# BUCK_BOOST_Converter.net
KiCad netlist of a schematic drawn in Altium Designer
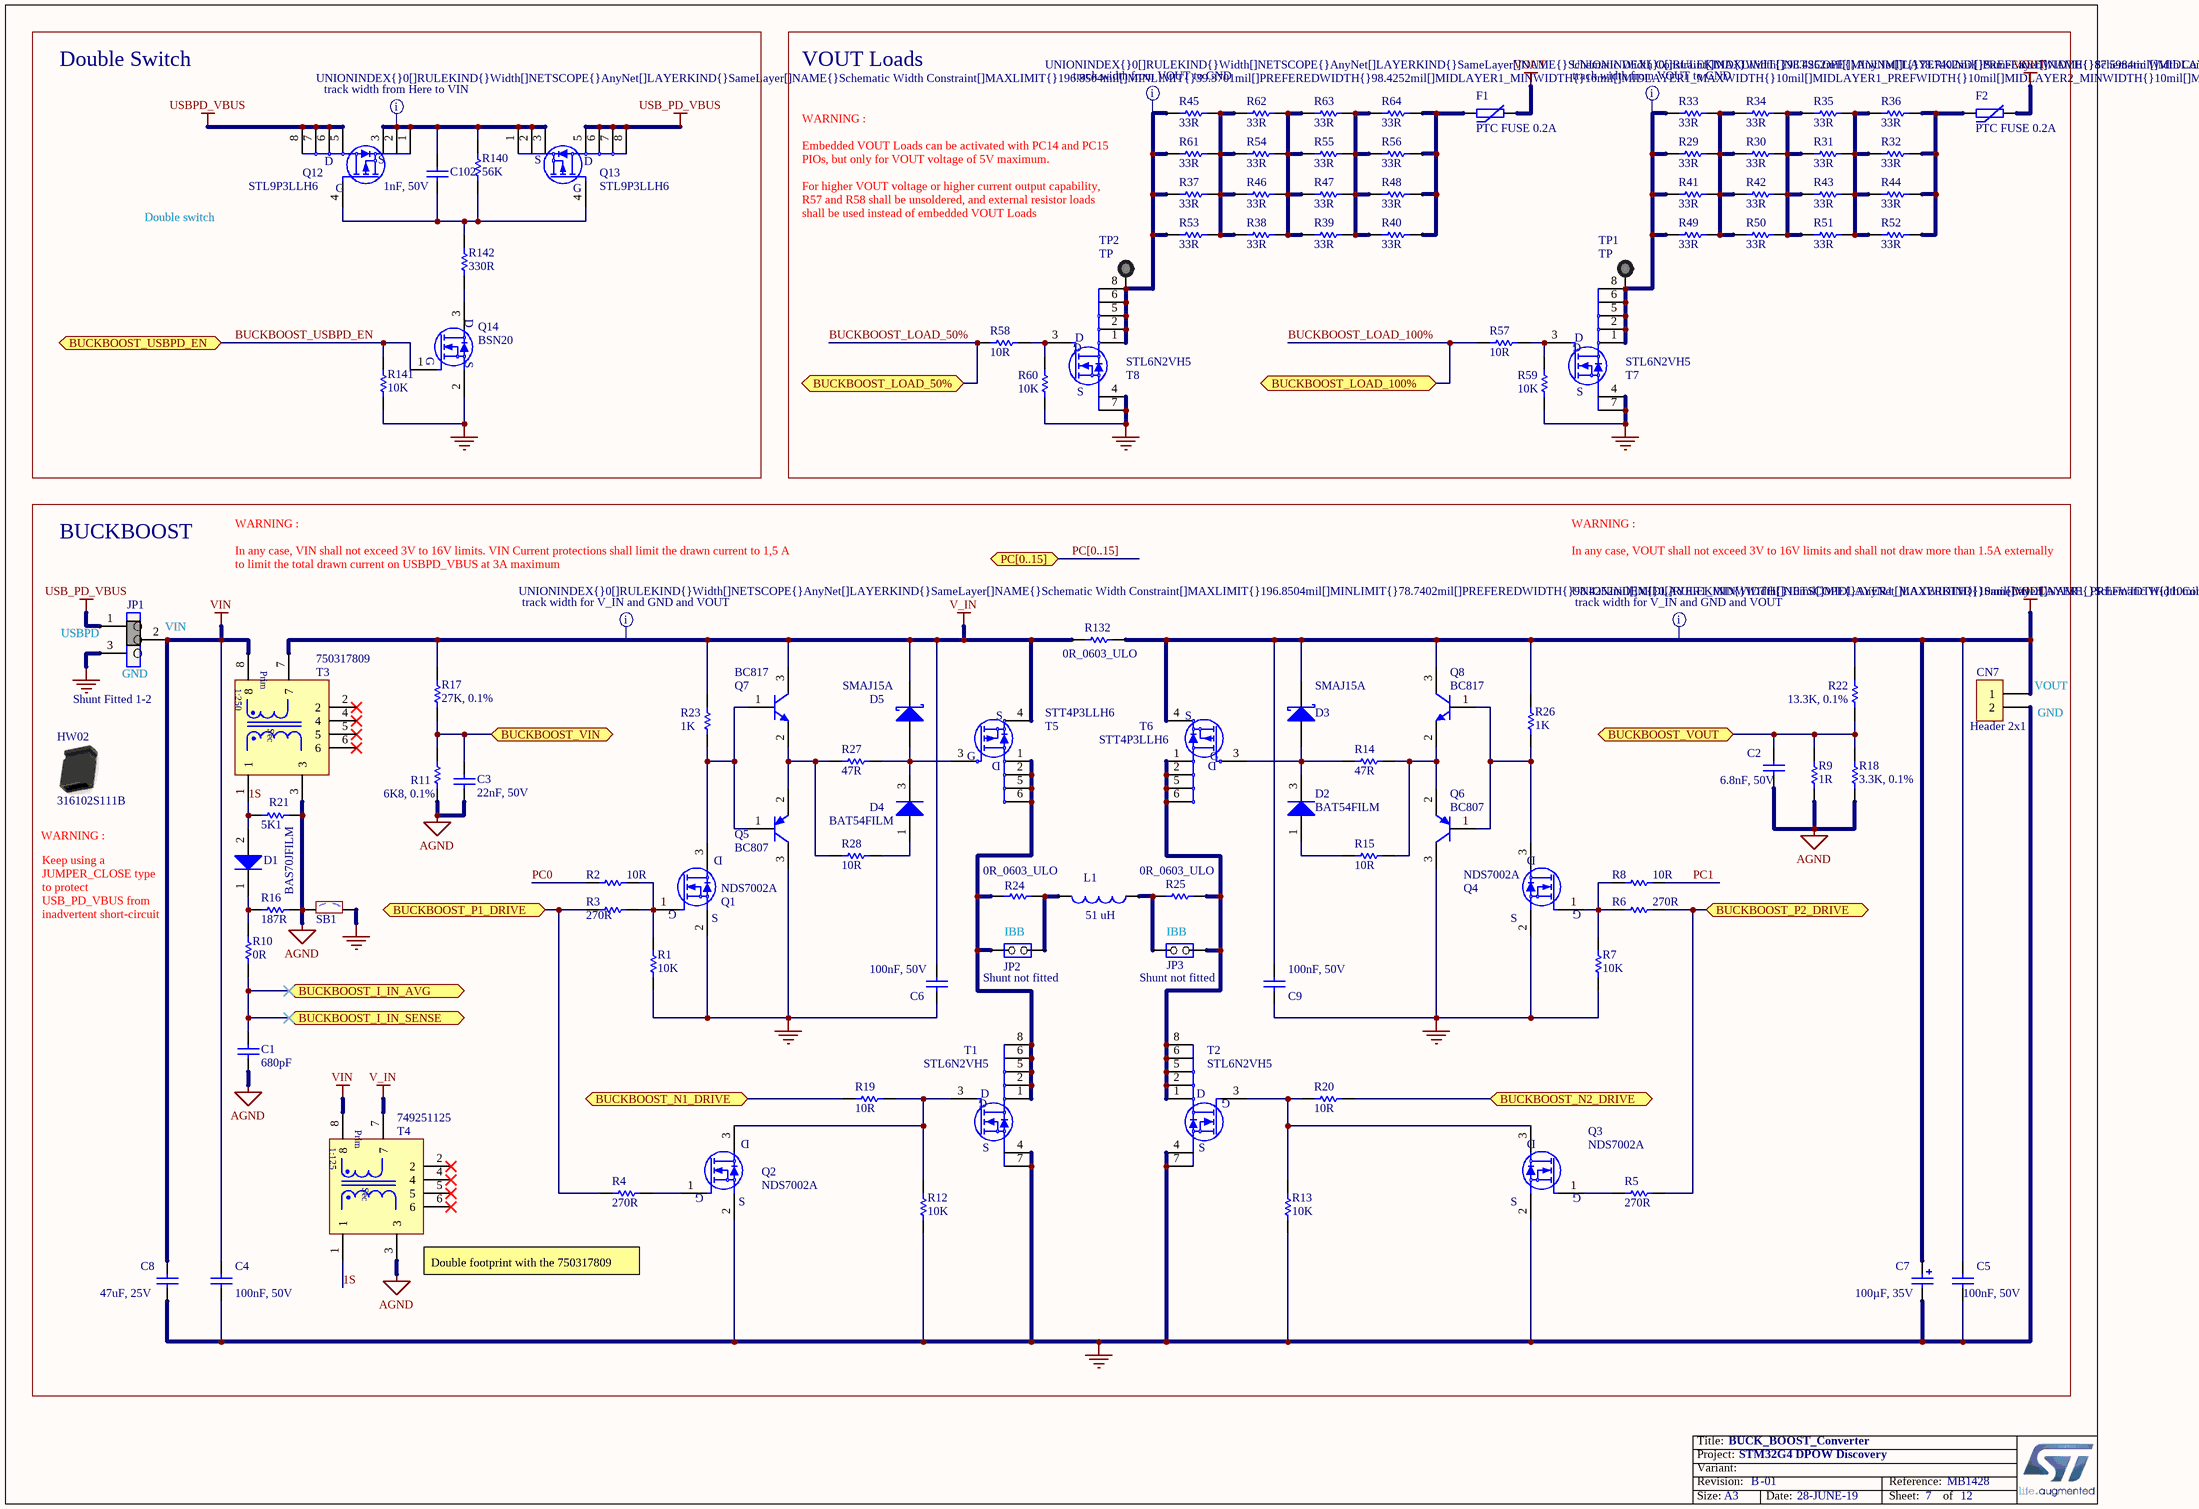
[diagram p0: BUCK_BOOST_Converter.SchDoc]

(export (version "E")
  (design (tool "Eeschema 10.0.6"))
  (components
    (comp (ref "C1")
      (value "680pF")
      (footprint "C0603_H0P8")
      (description "Capacitor, MLCC, 680pF, 16V, X7R, 10%, 0603, T=0.8mm")
      (fields
        (field (name "INTERNAL_PART_NUMBER") "MCD-01576")
        (field (name "MANUFACTURER_PART_NUMBER") "CC0603KRX7R7BB681")
        (field (name "PROVIDED_BY") "SUBCO")
      )
      (libsource (lib "MCD_PARTS_database") (part "Capacitor"))
    )
    (comp (ref "C2")
      (value "6.8nF, 50V")
      (footprint "C0603_H0P8")
      (description "Capacitor, MLCC, 6.8nF, 50V, X7R, 10%, 0603, T=0.8mm")
      (fields
        (field (name "INTERNAL_PART_NUMBER") "MCD-01544")
        (field (name "MANUFACTURER_PART_NUMBER") "CC0603KRX7R9BB682")
        (field (name "PROVIDED_BY") "SUBCO")
      )
      (libsource (lib "MCD_PARTS_database") (part "Capacitor"))
    )
    (comp (ref "C3")
      (value "22nF, 50V")
      (footprint "C0603")
      (description "Capacitor,22nF,50V,X7R,10%,0603")
      (fields
        (field (name "INTERNAL_PART_NUMBER") "MCD-01103")
        (field (name "MANUFACTURER_PART_NUMBER") "CC0603KRX7R9BB223")
        (field (name "PROVIDED_BY") "SUBCO")
      )
      (libsource (lib "MCD_PARTS_database") (part "Capacitor"))
    )
    (comp (ref "C4")
      (value "100nF, 50V")
      (footprint "C0805_H0P85")
      (description "Capacitor, MLCC, 100nF, 50V, X7R, 10%, 0805, T=0,85mm")
      (fields
        (field (name "INTERNAL_PART_NUMBER") "MCD-01525")
        (field (name "MANUFACTURER_PART_NUMBER") "CC0805KRX7R9BB104")
        (field (name "PROVIDED_BY") "SUBCO")
      )
      (libsource (lib "MCD_PARTS_database") (part "Capacitor"))
    )
    (comp (ref "C5")
      (value "100nF, 50V")
      (footprint "C0805_H0P85")
      (description "Capacitor, MLCC, 100nF, 50V, X7R, 10%, 0805, T=0,85mm")
      (fields
        (field (name "INTERNAL_PART_NUMBER") "MCD-01525")
        (field (name "MANUFACTURER_PART_NUMBER") "CC0805KRX7R9BB104")
        (field (name "PROVIDED_BY") "SUBCO")
      )
      (libsource (lib "MCD_PARTS_database") (part "Capacitor"))
    )
    (comp (ref "C6")
      (value "100nF, 50V")
      (footprint "C0805_H0P85")
      (description "Capacitor, MLCC, 100nF, 50V, X7R, 10%, 0805, T=0,85mm")
      (fields
        (field (name "INTERNAL_PART_NUMBER") "MCD-01525")
        (field (name "MANUFACTURER_PART_NUMBER") "CC0805KRX7R9BB104")
        (field (name "PROVIDED_BY") "SUBCO")
      )
      (libsource (lib "MCD_PARTS_database") (part "Capacitor"))
    )
    (comp (ref "C7")
      (value "100µF, 35V")
      (footprint "CPOL_WURTH_WCAP-ASLL_8X10P5")
      (description "Capacitor, Electrolytic, 100µF, 35V, 20%, SMT, D=8mm, T=10.5mm")
      (fields
        (field (name "INTERNAL_PART_NUMBER") "MCD-01683")
        (field (name "MANUFACTURER_PART_NUMBER") "865060553006")
        (field (name "PROVIDED_BY") "SUBCO")
      )
      (libsource (lib "MCD_PARTS_database") (part "Cap_POL_TANA"))
    )
    (comp (ref "C8")
      (value "47uF, 25V")
      (footprint "C1206_H1P6")
      (description "Capacitor, MLCC, 47uF, 25V, X5R, 20%, 1206, T=1,6mm")
      (fields
        (field (name "INTERNAL_PART_NUMBER") "MCD-01517")
        (field (name "MANUFACTURER_PART_NUMBER") "C3216X5R1E476M160AC ")
        (field (name "PROVIDED_BY") "SUBCO")
      )
      (libsource (lib "MCD_PARTS_database") (part "Capacitor"))
    )
    (comp (ref "C9")
      (value "100nF, 50V")
      (footprint "C0805_H0P85")
      (description "Capacitor, MLCC, 100nF, 50V, X7R, 10%, 0805, T=0,85mm")
      (fields
        (field (name "INTERNAL_PART_NUMBER") "MCD-01525")
        (field (name "MANUFACTURER_PART_NUMBER") "CC0805KRX7R9BB104")
        (field (name "PROVIDED_BY") "SUBCO")
      )
      (libsource (lib "MCD_PARTS_database") (part "Capacitor"))
    )
    (comp (ref "C102")
      (value "1nF, 50V")
      (footprint "C0805_H0P6")
      (description "Capacitor, MLCC, 1nF, 50V, X7R,10%, 0805, T=0,6mm")
      (fields
        (field (name "INTERNAL_PART_NUMBER") "MCD-01549")
        (field (name "MANUFACTURER_PART_NUMBER") "CC0805KRX7R9BB102")
        (field (name "PROVIDED_BY") "SUBCO")
      )
      (libsource (lib "MCD_PARTS_database") (part "Capacitor"))
    )
    (comp (ref "CN7")
      (value "Header 2x1")
      (footprint "CON_LYCONN_313102S141346")
      (description "Header 2x1, 2.54mm, VR, TH, height 5.84mm/7.50 mm, height total 15.84 mm")
      (fields
        (field (name "INTERNAL_PART_NUMBER") "MCD-01855")
        (field (name "MANUFACTURER_PART_NUMBER") "313102S1411584")
        (field (name "PROVIDED_BY") "SUBCO")
      )
      (libsource (lib "MCD_PARTS_database") (part "Header 2x1"))
    )
    (comp (ref "D1")
      (value "BAS70JFILM")
      (footprint "DIO_SOD323_1K_2A")
      (description "ultrafast and RF switching diode, VF = 0.41 V @ IF = 1mA; VR = 70V;")
      (fields
        (field (name "INTERNAL_PART_NUMBER") "MCD-01880")
        (field (name "MANUFACTURER") "STMICROELECTRONICS")
        (field (name "PROVIDED_BY") "SUBCO with ST control")
      )
      (libsource (lib "MCD_PARTS_database") (part "DIODE_1K_2A"))
    )
    (comp (ref "D2")
      (value "BAT54FILM")
      (footprint "DIO_SOT23_SC59_1A_2NC_3K_H1P4")
      (description "Single surface mount small signal schotky diode")
      (fields
        (field (name "INTERNAL_PART_NUMBER") "MCD-01524")
        (field (name "MANUFACTURER") "STMICROELECTRONICS")
        (field (name "PROVIDED_BY") "SUBCO with ST control")
      )
      (libsource (lib "MCD_PARTS_database") (part "DIODE_SOT23"))
    )
    (comp (ref "D3")
      (value "SMAJ15A")
      (footprint "DIO_SMA_1A_2K")
      (description "Transil unidirectional diode Vrm=15V, Vbr=16.7V(1mA), Vcl=32.5V(71A), SMA")
      (fields
        (field (name "INTERNAL_PART_NUMBER") "MCD-01522")
        (field (name "MANUFACTURER_PART_NUMBER") "SMAJ15A-TR")
        (field (name "PROVIDED_BY") "SUBCO with ST control")
      )
      (libsource (lib "MCD_PARTS_database") (part "ESD-TRANSIL-SMAJ_1A_2K"))
    )
    (comp (ref "D4")
      (value "BAT54FILM")
      (footprint "DIO_SOT23_SC59_1A_2NC_3K_H1P4")
      (description "Single surface mount small signal schotky diode")
      (fields
        (field (name "INTERNAL_PART_NUMBER") "MCD-01524")
        (field (name "MANUFACTURER") "STMICROELECTRONICS")
        (field (name "PROVIDED_BY") "SUBCO with ST control")
      )
      (libsource (lib "MCD_PARTS_database") (part "DIODE_SOT23"))
    )
    (comp (ref "D5")
      (value "SMAJ15A")
      (footprint "DIO_SMA_1A_2K")
      (description "Transil unidirectional diode Vrm=15V, Vbr=16.7V(1mA), Vcl=32.5V(71A), SMA")
      (fields
        (field (name "INTERNAL_PART_NUMBER") "MCD-01522")
        (field (name "MANUFACTURER_PART_NUMBER") "SMAJ15A-TR")
        (field (name "PROVIDED_BY") "SUBCO with ST control")
      )
      (libsource (lib "MCD_PARTS_database") (part "ESD-TRANSIL-SMAJ_1A_2K"))
    )
    (comp (ref "F1")
      (value "PTC FUSE 0.2A")
      (footprint "PTC_EATON_FUSE_PTS1812_H0P9")
      (description "SMD, PTC resettable fuse, IH:0.2A, IT:0.4A, Vdc_max:30V, Rmax:5 ohm")
      (fields
        (field (name "INTERNAL_PART_NUMBER") "MCD-01682")
        (field (name "MANUFACTURER_PART_NUMBER") "PTS181230V020")
        (field (name "PROVIDED_BY") "SUBCO")
      )
      (libsource (lib "MCD_PARTS_database") (part "0ZCG0260FF2C"))
    )
    (comp (ref "F2")
      (value "PTC FUSE 0.2A")
      (footprint "PTC_EATON_FUSE_PTS1812_H0P9")
      (description "SMD, PTC resettable fuse, IH:0.2A, IT:0.4A, Vdc_max:30V, Rmax:5 ohm")
      (fields
        (field (name "INTERNAL_PART_NUMBER") "MCD-01682")
        (field (name "MANUFACTURER_PART_NUMBER") "PTS181230V020")
        (field (name "PROVIDED_BY") "SUBCO")
      )
      (libsource (lib "MCD_PARTS_database") (part "0ZCG0260FF2C"))
    )
    (comp (ref "HW02")
      (value "316102S111B")
      (description "Jumper, height 6.5 mm, Black, 2.54mm, 3A, 20 mohm, close")
      (fields
        (field (name "INTERNAL_PART_NUMBER") "MCD-01864")
        (field (name "MANUFACTURER") "JIUBABA")
        (field (name "PROVIDED_BY") "SUBCO")
      )
      (libsource (lib "MCD_PARTS_database") (part "JUMPER_CLOSE"))
    )
    (comp (ref "JP1")
      (value "Shunt Fitted 1-2")
      (footprint "CON_SAMTEC_TSW-103-07-F-S")
      (description "Header, 3x1, 2,54mm, VR, TH, Height 5.84mm/2.54mm - Shunt Fitted 1-2 by default")
      (fields
        (field (name "INTERNAL_PART_NUMBER") "MCD-00684")
        (field (name "MANUFACTURER_PART_NUMBER") "TSW-103-07-F-S")
        (field (name "PROVIDED_BY") "SUBCO")
      )
      (libsource (lib "MCD_PARTS_database") (part "Jumper_Header 3x1 Fitted 1-2"))
    )
    (comp (ref "JP2")
      (value "Shunt not fitted")
      (footprint "CON_988-JIUBABA_313102S111116")
      (description "Header 2x1, 2.54mm, VR, TH, height 6 mm / 3 mm, total 11.6mm - Shunt not Fitted by default")
      (fields
        (field (name "INTERNAL_PART_NUMBER") "MCD-01660")
        (field (name "MANUFACTURER_PART_NUMBER") "313102S111116")
        (field (name "PROVIDED_BY") "SUBCO")
      )
      (libsource (lib "MCD_PARTS_database") (part "Jumper_Header 2x1"))
    )
    (comp (ref "JP3")
      (value "Shunt not fitted")
      (footprint "CON_988-JIUBABA_313102S111116")
      (description "Header 2x1, 2.54mm, VR, TH, height 6 mm / 3 mm, total 11.6mm - Shunt not Fitted by default")
      (fields
        (field (name "INTERNAL_PART_NUMBER") "MCD-01660")
        (field (name "MANUFACTURER_PART_NUMBER") "313102S111116")
        (field (name "PROVIDED_BY") "SUBCO")
      )
      (libsource (lib "MCD_PARTS_database") (part "Jumper_Header 2x1"))
    )
    (comp (ref "L1")
      (value "51 uH")
      (footprint "IND_SUNLORD_SWPA5040S")
      (description "SMD Wire wound power inductor, 51uH, 20%, Isat 1.2A, 380mohm, 5.0x5.0x4.0mm")
      (fields
        (field (name "INTERNAL_PART_NUMBER") "MCD-01787")
        (field (name "MANUFACTURER_PART_NUMBER") "SWPA5040S510MT")
        (field (name "PROVIDED_BY") "SUBCO")
      )
      (libsource (lib "MCD_PARTS_database") (part "Inductor"))
    )
    (comp (ref "Q1")
      (value "NDS7002A")
      (footprint "ICC_SOT23-3L_H1P12")
      (fields
        (field (name "INTERNAL_PART_NUMBER") "MCD-01518")
        (field (name "MANUFACTURER") "ON SEMICONDUCTOR")
        (field (name "PROVIDED_BY") "SUBCO")
      )
      (libsource (lib "MCD_PARTS_database") (part "MOSFET_N-CHANNEL"))
    )
    (comp (ref "Q2")
      (value "NDS7002A")
      (footprint "ICC_SOT23-3L_H1P12")
      (fields
        (field (name "INTERNAL_PART_NUMBER") "MCD-01518")
        (field (name "MANUFACTURER") "ON SEMICONDUCTOR")
        (field (name "PROVIDED_BY") "SUBCO")
      )
      (libsource (lib "MCD_PARTS_database") (part "MOSFET_N-CHANNEL"))
    )
    (comp (ref "Q3")
      (value "NDS7002A")
      (footprint "ICC_SOT23-3L_H1P12")
      (fields
        (field (name "INTERNAL_PART_NUMBER") "MCD-01518")
        (field (name "MANUFACTURER") "ON SEMICONDUCTOR")
        (field (name "PROVIDED_BY") "SUBCO")
      )
      (libsource (lib "MCD_PARTS_database") (part "MOSFET_N-CHANNEL"))
    )
    (comp (ref "Q4")
      (value "NDS7002A")
      (footprint "ICC_SOT23-3L_H1P12")
      (fields
        (field (name "INTERNAL_PART_NUMBER") "MCD-01518")
        (field (name "MANUFACTURER") "ON SEMICONDUCTOR")
        (field (name "PROVIDED_BY") "SUBCO")
      )
      (libsource (lib "MCD_PARTS_database") (part "MOSFET_N-CHANNEL"))
    )
    (comp (ref "Q5")
      (value "BC807")
      (footprint "ICC_SOT23-3L_H1P12")
      (description "Transistor Bipolar PNP, 45V, 500mA, 100MHz, 300mW, SOT23-3")
      (fields
        (field (name "INTERNAL_PART_NUMBER") "MCD-01527")
        (field (name "MANUFACTURER") "NEXPERIA")
        (field (name "PROVIDED_BY") "SUBCO")
      )
      (libsource (lib "MCD_PARTS_database") (part "PNP_SOT23"))
    )
    (comp (ref "Q6")
      (value "BC807")
      (footprint "ICC_SOT23-3L_H1P12")
      (description "Transistor Bipolar PNP, 45V, 500mA, 100MHz, 300mW, SOT23-3")
      (fields
        (field (name "INTERNAL_PART_NUMBER") "MCD-01527")
        (field (name "MANUFACTURER") "NEXPERIA")
        (field (name "PROVIDED_BY") "SUBCO")
      )
      (libsource (lib "MCD_PARTS_database") (part "PNP_SOT23"))
    )
    (comp (ref "Q7")
      (value "BC817")
      (footprint "NPN_SOT23")
      (description "Transistor Bipolar NPN, 45V, 500mA, 100MHz, 300mW, SOT23-3")
      (fields
        (field (name "INTERNAL_PART_NUMBER") "MCD-01526")
        (field (name "MANUFACTURER") "NEXPERIA")
        (field (name "PROVIDED_BY") "SUBCO")
      )
      (libsource (lib "MCD_PARTS_database") (part "9013-SOT23"))
    )
    (comp (ref "Q8")
      (value "BC817")
      (footprint "NPN_SOT23")
      (description "Transistor Bipolar NPN, 45V, 500mA, 100MHz, 300mW, SOT23-3")
      (fields
        (field (name "INTERNAL_PART_NUMBER") "MCD-01526")
        (field (name "MANUFACTURER") "NEXPERIA")
        (field (name "PROVIDED_BY") "SUBCO")
      )
      (libsource (lib "MCD_PARTS_database") (part "9013-SOT23"))
    )
    (comp (ref "Q12")
      (value "STL9P3LLH6")
      (footprint "MOS_POWERFLAT_3P3X3P3_P065")
      (description "Power Mosfet, P-channel,VDS -30V,RDS 12mohm typ,ID -9A")
      (fields
        (field (name "INTERNAL_PART_NUMBER") "MCD-01126")
        (field (name "MANUFACTURER") "STMICROELECTRONICS")
        (field (name "PROVIDED_BY") "SUBCO with ST control")
      )
      (libsource (lib "MCD_PARTS_database") (part "STL9P3LLH6"))
    )
    (comp (ref "Q13")
      (value "STL9P3LLH6")
      (footprint "MOS_POWERFLAT_3P3X3P3_P065")
      (description "Power Mosfet, P-channel,VDS -30V,RDS 12mohm typ,ID -9A")
      (fields
        (field (name "INTERNAL_PART_NUMBER") "MCD-01126")
        (field (name "MANUFACTURER") "STMICROELECTRONICS")
        (field (name "PROVIDED_BY") "SUBCO with ST control")
      )
      (libsource (lib "MCD_PARTS_database") (part "STL9P3LLH6"))
    )
    (comp (ref "Q14")
      (value "BSN20")
      (footprint "MOS_SOT23")
      (description "N-channel enhancement mode field-effect transistor")
      (fields
        (field (name "INTERNAL_PART_NUMBER") "MCD-00151")
        (field (name "MANUFACTURER") "NXP")
        (field (name "PROVIDED_BY") "SUBCO")
      )
      (libsource (lib "MCD_PARTS_database") (part "BSN20"))
    )
    (comp (ref "R1")
      (value "10K")
      (footprint "R0805")
      (description "Resistor,10K,0805,1%,1/8W")
      (fields
        (field (name "INTERNAL_PART_NUMBER") "MCD-01154")
        (field (name "MANUFACTURER_PART_NUMBER") "RC0805FR-0710KL")
        (field (name "PROVIDED_BY") "SUBCO")
      )
      (libsource (lib "MCD_PARTS_database") (part "Resistor"))
    )
    (comp (ref "R2")
      (value "10R")
      (footprint "R0805_H0P5")
      (description "Resistor,10R,0805,1%, 1/8W")
      (fields
        (field (name "INTERNAL_PART_NUMBER") "MCD-01548")
        (field (name "MANUFACTURER_PART_NUMBER") "RC0805FR-0710RL")
        (field (name "PROVIDED_BY") "SUBCO")
      )
      (libsource (lib "MCD_PARTS_database") (part "Resistor"))
    )
    (comp (ref "R3")
      (value "270R")
      (footprint "R0805_H0P5")
      (description "Resistor,270R,0805,1%,1/8W")
      (fields
        (field (name "INTERNAL_PART_NUMBER") "MCD-01537")
        (field (name "MANUFACTURER_PART_NUMBER") "RC0805FR-07270RL")
        (field (name "PROVIDED_BY") "SUBCO")
      )
      (libsource (lib "MCD_PARTS_database") (part "Resistor"))
    )
    (comp (ref "R4")
      (value "270R")
      (footprint "R0805_H0P5")
      (description "Resistor,270R,0805,1%,1/8W")
      (fields
        (field (name "INTERNAL_PART_NUMBER") "MCD-01537")
        (field (name "MANUFACTURER_PART_NUMBER") "RC0805FR-07270RL")
        (field (name "PROVIDED_BY") "SUBCO")
      )
      (libsource (lib "MCD_PARTS_database") (part "Resistor"))
    )
    (comp (ref "R5")
      (value "270R")
      (footprint "R0805_H0P5")
      (description "Resistor,270R,0805,1%,1/8W")
      (fields
        (field (name "INTERNAL_PART_NUMBER") "MCD-01537")
        (field (name "MANUFACTURER_PART_NUMBER") "RC0805FR-07270RL")
        (field (name "PROVIDED_BY") "SUBCO")
      )
      (libsource (lib "MCD_PARTS_database") (part "Resistor"))
    )
    (comp (ref "R6")
      (value "270R")
      (footprint "R0805_H0P5")
      (description "Resistor,270R,0805,1%,1/8W")
      (fields
        (field (name "INTERNAL_PART_NUMBER") "MCD-01537")
        (field (name "MANUFACTURER_PART_NUMBER") "RC0805FR-07270RL")
        (field (name "PROVIDED_BY") "SUBCO")
      )
      (libsource (lib "MCD_PARTS_database") (part "Resistor"))
    )
    (comp (ref "R7")
      (value "10K")
      (footprint "R0805")
      (description "Resistor,10K,0805,1%,1/8W")
      (fields
        (field (name "INTERNAL_PART_NUMBER") "MCD-01154")
        (field (name "MANUFACTURER_PART_NUMBER") "RC0805FR-0710KL")
        (field (name "PROVIDED_BY") "SUBCO")
      )
      (libsource (lib "MCD_PARTS_database") (part "Resistor"))
    )
    (comp (ref "R8")
      (value "10R")
      (footprint "R0805_H0P5")
      (description "Resistor,10R,0805,1%, 1/8W")
      (fields
        (field (name "INTERNAL_PART_NUMBER") "MCD-01548")
        (field (name "MANUFACTURER_PART_NUMBER") "RC0805FR-0710RL")
        (field (name "PROVIDED_BY") "SUBCO")
      )
      (libsource (lib "MCD_PARTS_database") (part "Resistor"))
    )
    (comp (ref "R9")
      (value "1R")
      (footprint "R1206_H0P55")
      (description "Resistor, 1R, 1206, 0.1%, 1/4W")
      (fields
        (field (name "INTERNAL_PART_NUMBER") "MCD-01546")
        (field (name "MANUFACTURER_PART_NUMBER") "RT1206BRD071RL")
        (field (name "PROVIDED_BY") "SUBCO")
      )
      (libsource (lib "MCD_PARTS_database") (part "Resistor"))
    )
    (comp (ref "R10")
      (value "0R")
      (footprint "R0603")
      (description "Resistor,0R,0603,5%,1/10W")
      (fields
        (field (name "INTERNAL_PART_NUMBER") "MCD-00056")
        (field (name "MANUFACTURER_PART_NUMBER") "RC0603JR-070RL")
        (field (name "PROVIDED_BY") "SUBCO")
      )
      (libsource (lib "MCD_PARTS_database") (part "Resistor"))
    )
    (comp (ref "R11")
      (value "6K8, 0.1%")
      (footprint "R0805")
      (description "Resistor, 6K8, 0805, 0.1%, 1/8W, 50ppm")
      (fields
        (field (name "INTERNAL_PART_NUMBER") "MCD-01654")
        (field (name "MANUFACTURER_PART_NUMBER") "AR05BTD6801")
        (field (name "PROVIDED_BY") "SUBCO")
      )
      (libsource (lib "MCD_PARTS_database") (part "Resistor"))
    )
    (comp (ref "R12")
      (value "10K")
      (footprint "R0805")
      (description "Resistor,10K,0805,1%,1/8W")
      (fields
        (field (name "INTERNAL_PART_NUMBER") "MCD-01154")
        (field (name "MANUFACTURER_PART_NUMBER") "RC0805FR-0710KL")
        (field (name "PROVIDED_BY") "SUBCO")
      )
      (libsource (lib "MCD_PARTS_database") (part "Resistor"))
    )
    (comp (ref "R13")
      (value "10K")
      (footprint "R0805")
      (description "Resistor,10K,0805,1%,1/8W")
      (fields
        (field (name "INTERNAL_PART_NUMBER") "MCD-01154")
        (field (name "MANUFACTURER_PART_NUMBER") "RC0805FR-0710KL")
        (field (name "PROVIDED_BY") "SUBCO")
      )
      (libsource (lib "MCD_PARTS_database") (part "Resistor"))
    )
    (comp (ref "R14")
      (value "47R")
      (footprint "R0805_H0P5")
      (description "Resistor,47R,0805,1%,1/8W")
      (fields
        (field (name "INTERNAL_PART_NUMBER") "MCD-01547")
        (field (name "MANUFACTURER_PART_NUMBER") "RC0805FR-0747RL")
        (field (name "PROVIDED_BY") "SUBCO")
      )
      (libsource (lib "MCD_PARTS_database") (part "Resistor"))
    )
    (comp (ref "R15")
      (value "10R")
      (footprint "R0805_H0P5")
      (description "Resistor,10R,0805,1%, 1/8W")
      (fields
        (field (name "INTERNAL_PART_NUMBER") "MCD-01548")
        (field (name "MANUFACTURER_PART_NUMBER") "RC0805FR-0710RL")
        (field (name "PROVIDED_BY") "SUBCO")
      )
      (libsource (lib "MCD_PARTS_database") (part "Resistor"))
    )
    (comp (ref "R16")
      (value "187R")
      (footprint "R1206_H0P55")
      (description "Resistor,187R,1206,1%,1/4W")
      (fields
        (field (name "INTERNAL_PART_NUMBER") "MCD-01881")
        (field (name "MANUFACTURER_PART_NUMBER") "RC1206FR-07187RL")
        (field (name "PROVIDED_BY") "SUBCO")
      )
      (libsource (lib "MCD_PARTS_database") (part "Resistor"))
    )
    (comp (ref "R17")
      (value "27K, 0.1%")
      (footprint "R0805")
      (description "Resistor, 27K, 0805, 0.1%, 1/8W, 50ppm")
      (fields
        (field (name "INTERNAL_PART_NUMBER") "MCD-01652")
        (field (name "MANUFACTURER_PART_NUMBER") "AR05BTD2702")
        (field (name "PROVIDED_BY") "SUBCO")
      )
      (libsource (lib "MCD_PARTS_database") (part "Resistor"))
    )
    (comp (ref "R18")
      (value "3.3K, 0.1%")
      (footprint "R0805")
      (description "Resistor, 3K3, 0805, 0.1%, 1/8W, 50ppm")
      (fields
        (field (name "INTERNAL_PART_NUMBER") "MCD-01653")
        (field (name "MANUFACTURER_PART_NUMBER") "AR05BTD3301")
        (field (name "PROVIDED_BY") "SUBCO")
      )
      (libsource (lib "MCD_PARTS_database") (part "Resistor"))
    )
    (comp (ref "R19")
      (value "10R")
      (footprint "R0805_H0P5")
      (description "Resistor,10R,0805,1%, 1/8W")
      (fields
        (field (name "INTERNAL_PART_NUMBER") "MCD-01548")
        (field (name "MANUFACTURER_PART_NUMBER") "RC0805FR-0710RL")
        (field (name "PROVIDED_BY") "SUBCO")
      )
      (libsource (lib "MCD_PARTS_database") (part "Resistor"))
    )
    (comp (ref "R20")
      (value "10R")
      (footprint "R0805_H0P5")
      (description "Resistor,10R,0805,1%, 1/8W")
      (fields
        (field (name "INTERNAL_PART_NUMBER") "MCD-01548")
        (field (name "MANUFACTURER_PART_NUMBER") "RC0805FR-0710RL")
        (field (name "PROVIDED_BY") "SUBCO")
      )
      (libsource (lib "MCD_PARTS_database") (part "Resistor"))
    )
    (comp (ref "R21")
      (value "5K1")
      (footprint "R0603")
      (description "Resistor,5K1,0603,1%,1/10W")
      (fields
        (field (name "INTERNAL_PART_NUMBER") "MCD-01882")
        (field (name "MANUFACTURER_PART_NUMBER") "RC0603FR-075K1L")
        (field (name "PROVIDED_BY") "SUBCO")
      )
      (libsource (lib "MCD_PARTS_database") (part "Resistor"))
    )
    (comp (ref "R22")
      (value "13.3K, 0.1%")
      (footprint "R0805")
      (description "Resistor, 13K3, 0805, 0.1%, 1/8W, 50ppm")
      (fields
        (field (name "INTERNAL_PART_NUMBER") "MCD-01649")
        (field (name "MANUFACTURER_PART_NUMBER") "AR05BTD1332")
        (field (name "PROVIDED_BY") "SUBCO")
      )
      (libsource (lib "MCD_PARTS_database") (part "Resistor"))
    )
    (comp (ref "R23")
      (value "1K")
      (footprint "R0603")
      (description "Resistor,1K,0603,1%,1/10W")
      (fields
        (field (name "INTERNAL_PART_NUMBER") "MCD-00070")
        (field (name "MANUFACTURER_PART_NUMBER") "RC0603FR-071KL")
        (field (name "PROVIDED_BY") "SUBCO")
      )
      (libsource (lib "MCD_PARTS_database") (part "Resistor"))
    )
    (comp (ref "R24")
      (value "0R_0603_ULO")
      (footprint "R0603")
      (description "Resistor,0R,0603,ULO")
      (fields
        (field (name "INTERNAL_PART_NUMBER") "MCD-00181")
        (field (name "MANUFACTURER_PART_NUMBER") "PMR03EZPJ000")
        (field (name "PROVIDED_BY") "SUBCO")
      )
      (libsource (lib "MCD_PARTS_database") (part "Resistor"))
    )
    (comp (ref "R25")
      (value "0R_0603_ULO")
      (footprint "R0603")
      (description "Resistor,0R,0603,ULO")
      (fields
        (field (name "INTERNAL_PART_NUMBER") "MCD-00181")
        (field (name "MANUFACTURER_PART_NUMBER") "PMR03EZPJ000")
        (field (name "PROVIDED_BY") "SUBCO")
      )
      (libsource (lib "MCD_PARTS_database") (part "Resistor"))
    )
    (comp (ref "R26")
      (value "1K")
      (footprint "R0603")
      (description "Resistor,1K,0603,1%,1/10W")
      (fields
        (field (name "INTERNAL_PART_NUMBER") "MCD-00070")
        (field (name "MANUFACTURER_PART_NUMBER") "RC0603FR-071KL")
        (field (name "PROVIDED_BY") "SUBCO")
      )
      (libsource (lib "MCD_PARTS_database") (part "Resistor"))
    )
    (comp (ref "R27")
      (value "47R")
      (footprint "R0805_H0P5")
      (description "Resistor,47R,0805,1%,1/8W")
      (fields
        (field (name "INTERNAL_PART_NUMBER") "MCD-01547")
        (field (name "MANUFACTURER_PART_NUMBER") "RC0805FR-0747RL")
        (field (name "PROVIDED_BY") "SUBCO")
      )
      (libsource (lib "MCD_PARTS_database") (part "Resistor"))
    )
    (comp (ref "R28")
      (value "10R")
      (footprint "R0805_H0P5")
      (description "Resistor,10R,0805,1%, 1/8W")
      (fields
        (field (name "INTERNAL_PART_NUMBER") "MCD-01548")
        (field (name "MANUFACTURER_PART_NUMBER") "RC0805FR-0710RL")
        (field (name "PROVIDED_BY") "SUBCO")
      )
      (libsource (lib "MCD_PARTS_database") (part "Resistor"))
    )
    (comp (ref "R29")
      (value "33R")
      (footprint "R1206_H0P55")
      (description "Resistor,33R,1206,1%,1/4W")
      (fields
        (field (name "INTERNAL_PART_NUMBER") "MCD-01681")
        (field (name "MANUFACTURER_PART_NUMBER") "RC1206FR-0733RL")
        (field (name "PROVIDED_BY") "SUBCO")
      )
      (libsource (lib "MCD_PARTS_database") (part "Resistor"))
    )
    (comp (ref "R30")
      (value "33R")
      (footprint "R1206_H0P55")
      (description "Resistor,33R,1206,1%,1/4W")
      (fields
        (field (name "INTERNAL_PART_NUMBER") "MCD-01681")
        (field (name "MANUFACTURER_PART_NUMBER") "RC1206FR-0733RL")
        (field (name "PROVIDED_BY") "SUBCO")
      )
      (libsource (lib "MCD_PARTS_database") (part "Resistor"))
    )
    (comp (ref "R31")
      (value "33R")
      (footprint "R1206_H0P55")
      (description "Resistor,33R,1206,1%,1/4W")
      (fields
        (field (name "INTERNAL_PART_NUMBER") "MCD-01681")
        (field (name "MANUFACTURER_PART_NUMBER") "RC1206FR-0733RL")
        (field (name "PROVIDED_BY") "SUBCO")
      )
      (libsource (lib "MCD_PARTS_database") (part "Resistor"))
    )
    (comp (ref "R32")
      (value "33R")
      (footprint "R1206_H0P55")
      (description "Resistor,33R,1206,1%,1/4W")
      (fields
        (field (name "INTERNAL_PART_NUMBER") "MCD-01681")
        (field (name "MANUFACTURER_PART_NUMBER") "RC1206FR-0733RL")
        (field (name "PROVIDED_BY") "SUBCO")
      )
      (libsource (lib "MCD_PARTS_database") (part "Resistor"))
    )
    (comp (ref "R33")
      (value "33R")
      (footprint "R1206_H0P55")
      (description "Resistor,33R,1206,1%,1/4W")
      (fields
        (field (name "INTERNAL_PART_NUMBER") "MCD-01681")
        (field (name "MANUFACTURER_PART_NUMBER") "RC1206FR-0733RL")
        (field (name "PROVIDED_BY") "SUBCO")
      )
      (libsource (lib "MCD_PARTS_database") (part "Resistor"))
    )
    (comp (ref "R34")
      (value "33R")
      (footprint "R1206_H0P55")
      (description "Resistor,33R,1206,1%,1/4W")
      (fields
        (field (name "INTERNAL_PART_NUMBER") "MCD-01681")
        (field (name "MANUFACTURER_PART_NUMBER") "RC1206FR-0733RL")
        (field (name "PROVIDED_BY") "SUBCO")
      )
      (libsource (lib "MCD_PARTS_database") (part "Resistor"))
    )
    (comp (ref "R35")
      (value "33R")
      (footprint "R1206_H0P55")
      (description "Resistor,33R,1206,1%,1/4W")
      (fields
        (field (name "INTERNAL_PART_NUMBER") "MCD-01681")
        (field (name "MANUFACTURER_PART_NUMBER") "RC1206FR-0733RL")
        (field (name "PROVIDED_BY") "SUBCO")
      )
      (libsource (lib "MCD_PARTS_database") (part "Resistor"))
    )
    (comp (ref "R36")
      (value "33R")
      (footprint "R1206_H0P55")
      (description "Resistor,33R,1206,1%,1/4W")
      (fields
        (field (name "INTERNAL_PART_NUMBER") "MCD-01681")
        (field (name "MANUFACTURER_PART_NUMBER") "RC1206FR-0733RL")
        (field (name "PROVIDED_BY") "SUBCO")
      )
      (libsource (lib "MCD_PARTS_database") (part "Resistor"))
    )
    (comp (ref "R37")
      (value "33R")
      (footprint "R1206_H0P55")
      (description "Resistor,33R,1206,1%,1/4W")
      (fields
        (field (name "INTERNAL_PART_NUMBER") "MCD-01681")
        (field (name "MANUFACTURER_PART_NUMBER") "RC1206FR-0733RL")
        (field (name "PROVIDED_BY") "SUBCO")
      )
      (libsource (lib "MCD_PARTS_database") (part "Resistor"))
    )
    (comp (ref "R38")
      (value "33R")
      (footprint "R1206_H0P55")
      (description "Resistor,33R,1206,1%,1/4W")
      (fields
        (field (name "INTERNAL_PART_NUMBER") "MCD-01681")
        (field (name "MANUFACTURER_PART_NUMBER") "RC1206FR-0733RL")
        (field (name "PROVIDED_BY") "SUBCO")
      )
      (libsource (lib "MCD_PARTS_database") (part "Resistor"))
    )
    (comp (ref "R39")
      (value "33R")
      (footprint "R1206_H0P55")
      (description "Resistor,33R,1206,1%,1/4W")
      (fields
        (field (name "INTERNAL_PART_NUMBER") "MCD-01681")
        (field (name "MANUFACTURER_PART_NUMBER") "RC1206FR-0733RL")
        (field (name "PROVIDED_BY") "SUBCO")
      )
      (libsource (lib "MCD_PARTS_database") (part "Resistor"))
    )
    (comp (ref "R40")
      (value "33R")
      (footprint "R1206_H0P55")
      (description "Resistor,33R,1206,1%,1/4W")
      (fields
        (field (name "INTERNAL_PART_NUMBER") "MCD-01681")
        (field (name "MANUFACTURER_PART_NUMBER") "RC1206FR-0733RL")
        (field (name "PROVIDED_BY") "SUBCO")
      )
      (libsource (lib "MCD_PARTS_database") (part "Resistor"))
    )
    (comp (ref "R41")
      (value "33R")
      (footprint "R1206_H0P55")
      (description "Resistor,33R,1206,1%,1/4W")
      (fields
        (field (name "INTERNAL_PART_NUMBER") "MCD-01681")
        (field (name "MANUFACTURER_PART_NUMBER") "RC1206FR-0733RL")
        (field (name "PROVIDED_BY") "SUBCO")
      )
      (libsource (lib "MCD_PARTS_database") (part "Resistor"))
    )
    (comp (ref "R42")
      (value "33R")
      (footprint "R1206_H0P55")
      (description "Resistor,33R,1206,1%,1/4W")
      (fields
        (field (name "INTERNAL_PART_NUMBER") "MCD-01681")
        (field (name "MANUFACTURER_PART_NUMBER") "RC1206FR-0733RL")
        (field (name "PROVIDED_BY") "SUBCO")
      )
      (libsource (lib "MCD_PARTS_database") (part "Resistor"))
    )
    (comp (ref "R43")
      (value "33R")
      (footprint "R1206_H0P55")
      (description "Resistor,33R,1206,1%,1/4W")
      (fields
        (field (name "INTERNAL_PART_NUMBER") "MCD-01681")
        (field (name "MANUFACTURER_PART_NUMBER") "RC1206FR-0733RL")
        (field (name "PROVIDED_BY") "SUBCO")
      )
      (libsource (lib "MCD_PARTS_database") (part "Resistor"))
    )
    (comp (ref "R44")
      (value "33R")
      (footprint "R1206_H0P55")
      (description "Resistor,33R,1206,1%,1/4W")
      (fields
        (field (name "INTERNAL_PART_NUMBER") "MCD-01681")
        (field (name "MANUFACTURER_PART_NUMBER") "RC1206FR-0733RL")
        (field (name "PROVIDED_BY") "SUBCO")
      )
      (libsource (lib "MCD_PARTS_database") (part "Resistor"))
    )
    (comp (ref "R45")
      (value "33R")
      (footprint "R1206_H0P55")
      (description "Resistor,33R,1206,1%,1/4W")
      (fields
        (field (name "INTERNAL_PART_NUMBER") "MCD-01681")
        (field (name "MANUFACTURER_PART_NUMBER") "RC1206FR-0733RL")
        (field (name "PROVIDED_BY") "SUBCO")
      )
      (libsource (lib "MCD_PARTS_database") (part "Resistor"))
    )
    (comp (ref "R46")
      (value "33R")
      (footprint "R1206_H0P55")
      (description "Resistor,33R,1206,1%,1/4W")
      (fields
        (field (name "INTERNAL_PART_NUMBER") "MCD-01681")
        (field (name "MANUFACTURER_PART_NUMBER") "RC1206FR-0733RL")
        (field (name "PROVIDED_BY") "SUBCO")
      )
      (libsource (lib "MCD_PARTS_database") (part "Resistor"))
    )
    (comp (ref "R47")
      (value "33R")
      (footprint "R1206_H0P55")
      (description "Resistor,33R,1206,1%,1/4W")
      (fields
        (field (name "INTERNAL_PART_NUMBER") "MCD-01681")
        (field (name "MANUFACTURER_PART_NUMBER") "RC1206FR-0733RL")
        (field (name "PROVIDED_BY") "SUBCO")
      )
      (libsource (lib "MCD_PARTS_database") (part "Resistor"))
    )
    (comp (ref "R48")
      (value "33R")
      (footprint "R1206_H0P55")
      (description "Resistor,33R,1206,1%,1/4W")
      (fields
        (field (name "INTERNAL_PART_NUMBER") "MCD-01681")
        (field (name "MANUFACTURER_PART_NUMBER") "RC1206FR-0733RL")
        (field (name "PROVIDED_BY") "SUBCO")
      )
      (libsource (lib "MCD_PARTS_database") (part "Resistor"))
    )
    (comp (ref "R49")
      (value "33R")
      (footprint "R1206_H0P55")
      (description "Resistor,33R,1206,1%,1/4W")
      (fields
        (field (name "INTERNAL_PART_NUMBER") "MCD-01681")
        (field (name "MANUFACTURER_PART_NUMBER") "RC1206FR-0733RL")
        (field (name "PROVIDED_BY") "SUBCO")
      )
      (libsource (lib "MCD_PARTS_database") (part "Resistor"))
    )
    (comp (ref "R50")
      (value "33R")
      (footprint "R1206_H0P55")
      (description "Resistor,33R,1206,1%,1/4W")
      (fields
        (field (name "INTERNAL_PART_NUMBER") "MCD-01681")
        (field (name "MANUFACTURER_PART_NUMBER") "RC1206FR-0733RL")
        (field (name "PROVIDED_BY") "SUBCO")
      )
      (libsource (lib "MCD_PARTS_database") (part "Resistor"))
    )
    (comp (ref "R51")
      (value "33R")
      (footprint "R1206_H0P55")
      (description "Resistor,33R,1206,1%,1/4W")
      (fields
        (field (name "INTERNAL_PART_NUMBER") "MCD-01681")
        (field (name "MANUFACTURER_PART_NUMBER") "RC1206FR-0733RL")
        (field (name "PROVIDED_BY") "SUBCO")
      )
      (libsource (lib "MCD_PARTS_database") (part "Resistor"))
    )
    (comp (ref "R52")
      (value "33R")
      (footprint "R1206_H0P55")
      (description "Resistor,33R,1206,1%,1/4W")
      (fields
        (field (name "INTERNAL_PART_NUMBER") "MCD-01681")
        (field (name "MANUFACTURER_PART_NUMBER") "RC1206FR-0733RL")
        (field (name "PROVIDED_BY") "SUBCO")
      )
      (libsource (lib "MCD_PARTS_database") (part "Resistor"))
    )
    (comp (ref "R53")
      (value "33R")
      (footprint "R1206_H0P55")
      (description "Resistor,33R,1206,1%,1/4W")
      (fields
        (field (name "INTERNAL_PART_NUMBER") "MCD-01681")
        (field (name "MANUFACTURER_PART_NUMBER") "RC1206FR-0733RL")
        (field (name "PROVIDED_BY") "SUBCO")
      )
      (libsource (lib "MCD_PARTS_database") (part "Resistor"))
    )
    (comp (ref "R54")
      (value "33R")
      (footprint "R1206_H0P55")
      (description "Resistor,33R,1206,1%,1/4W")
      (fields
        (field (name "INTERNAL_PART_NUMBER") "MCD-01681")
        (field (name "MANUFACTURER_PART_NUMBER") "RC1206FR-0733RL")
        (field (name "PROVIDED_BY") "SUBCO")
      )
      (libsource (lib "MCD_PARTS_database") (part "Resistor"))
    )
    (comp (ref "R55")
      (value "33R")
      (footprint "R1206_H0P55")
      (description "Resistor,33R,1206,1%,1/4W")
      (fields
        (field (name "INTERNAL_PART_NUMBER") "MCD-01681")
        (field (name "MANUFACTURER_PART_NUMBER") "RC1206FR-0733RL")
        (field (name "PROVIDED_BY") "SUBCO")
      )
      (libsource (lib "MCD_PARTS_database") (part "Resistor"))
    )
    (comp (ref "R56")
      (value "33R")
      (footprint "R1206_H0P55")
      (description "Resistor,33R,1206,1%,1/4W")
      (fields
        (field (name "INTERNAL_PART_NUMBER") "MCD-01681")
        (field (name "MANUFACTURER_PART_NUMBER") "RC1206FR-0733RL")
        (field (name "PROVIDED_BY") "SUBCO")
      )
      (libsource (lib "MCD_PARTS_database") (part "Resistor"))
    )
    (comp (ref "R57")
      (value "10R")
      (footprint "R0805_H0P5")
      (description "Resistor,10R,0805,1%, 1/8W")
      (fields
        (field (name "INTERNAL_PART_NUMBER") "MCD-01548")
        (field (name "MANUFACTURER_PART_NUMBER") "RC0805FR-0710RL")
        (field (name "PROVIDED_BY") "SUBCO")
      )
      (libsource (lib "MCD_PARTS_database") (part "Resistor"))
    )
    (comp (ref "R58")
      (value "10R")
      (footprint "R0805_H0P5")
      (description "Resistor,10R,0805,1%, 1/8W")
      (fields
        (field (name "INTERNAL_PART_NUMBER") "MCD-01548")
        (field (name "MANUFACTURER_PART_NUMBER") "RC0805FR-0710RL")
        (field (name "PROVIDED_BY") "SUBCO")
      )
      (libsource (lib "MCD_PARTS_database") (part "Resistor"))
    )
    (comp (ref "R59")
      (value "10K")
      (footprint "R0603")
      (description "Resistor,10K,0603,1%,1/10W")
      (fields
        (field (name "INTERNAL_PART_NUMBER") "MCD-00220")
        (field (name "MANUFACTURER_PART_NUMBER") "RC0603FR-0710KL")
        (field (name "PROVIDED_BY") "SUBCO")
      )
      (libsource (lib "MCD_PARTS_database") (part "Resistor"))
    )
    (comp (ref "R60")
      (value "10K")
      (footprint "R0603")
      (description "Resistor,10K,0603,1%,1/10W")
      (fields
        (field (name "INTERNAL_PART_NUMBER") "MCD-00220")
        (field (name "MANUFACTURER_PART_NUMBER") "RC0603FR-0710KL")
        (field (name "PROVIDED_BY") "SUBCO")
      )
      (libsource (lib "MCD_PARTS_database") (part "Resistor"))
    )
    (comp (ref "R61")
      (value "33R")
      (footprint "R1206_H0P55")
      (description "Resistor,33R,1206,1%,1/4W")
      (fields
        (field (name "INTERNAL_PART_NUMBER") "MCD-01681")
        (field (name "MANUFACTURER_PART_NUMBER") "RC1206FR-0733RL")
        (field (name "PROVIDED_BY") "SUBCO")
      )
      (libsource (lib "MCD_PARTS_database") (part "Resistor"))
    )
    (comp (ref "R62")
      (value "33R")
      (footprint "R1206_H0P55")
      (description "Resistor,33R,1206,1%,1/4W")
      (fields
        (field (name "INTERNAL_PART_NUMBER") "MCD-01681")
        (field (name "MANUFACTURER_PART_NUMBER") "RC1206FR-0733RL")
        (field (name "PROVIDED_BY") "SUBCO")
      )
      (libsource (lib "MCD_PARTS_database") (part "Resistor"))
    )
    (comp (ref "R63")
      (value "33R")
      (footprint "R1206_H0P55")
      (description "Resistor,33R,1206,1%,1/4W")
      (fields
        (field (name "INTERNAL_PART_NUMBER") "MCD-01681")
        (field (name "MANUFACTURER_PART_NUMBER") "RC1206FR-0733RL")
        (field (name "PROVIDED_BY") "SUBCO")
      )
      (libsource (lib "MCD_PARTS_database") (part "Resistor"))
    )
    (comp (ref "R64")
      (value "33R")
      (footprint "R1206_H0P55")
      (description "Resistor,33R,1206,1%,1/4W")
      (fields
        (field (name "INTERNAL_PART_NUMBER") "MCD-01681")
        (field (name "MANUFACTURER_PART_NUMBER") "RC1206FR-0733RL")
        (field (name "PROVIDED_BY") "SUBCO")
      )
      (libsource (lib "MCD_PARTS_database") (part "Resistor"))
    )
    (comp (ref "R132")
      (value "0R_0603_ULO")
      (footprint "R0603")
      (description "Resistor,0R,0603,ULO")
      (fields
        (field (name "INTERNAL_PART_NUMBER") "MCD-00181")
        (field (name "MANUFACTURER_PART_NUMBER") "PMR03EZPJ000")
        (field (name "PROVIDED_BY") "SUBCO")
      )
      (libsource (lib "MCD_PARTS_database") (part "Resistor"))
    )
    (comp (ref "R140")
      (value "56K")
      (footprint "R0603")
      (description "Resistor,56K,0603,1%,1/10W")
      (fields
        (field (name "INTERNAL_PART_NUMBER") "MCD-00494")
        (field (name "MANUFACTURER_PART_NUMBER") "RC0603FR-0756KL")
        (field (name "PROVIDED_BY") "SUBCO")
      )
      (libsource (lib "MCD_PARTS_database") (part "Resistor"))
    )
    (comp (ref "R141")
      (value "10K")
      (footprint "R0603")
      (description "Resistor,10K,0603,1%,1/10W")
      (fields
        (field (name "INTERNAL_PART_NUMBER") "MCD-00220")
        (field (name "MANUFACTURER_PART_NUMBER") "RC0603FR-0710KL")
        (field (name "PROVIDED_BY") "SUBCO")
      )
      (libsource (lib "MCD_PARTS_database") (part "Resistor"))
    )
    (comp (ref "R142")
      (value "330R")
      (footprint "R0603")
      (description "Resistor,330R,0603,1%,1/10W")
      (fields
        (field (name "INTERNAL_PART_NUMBER") "MCD-00197")
        (field (name "MANUFACTURER_PART_NUMBER") "RC0603FR-07330RL")
        (field (name "PROVIDED_BY") "SUBCO")
      )
      (libsource (lib "MCD_PARTS_database") (part "Resistor"))
    )
    (comp (ref "SB1")
      (value "~")
      (footprint "SOLDER-BRIDGE_R0603-0R")
      (description "Solder Bridge OFF")
      (fields
        (field (name "INTERNAL_PART_NUMBER") "MCD-00072")
        (field (name "MANUFACTURER_PART_NUMBER") "RC0603JR-070RL")
        (field (name "PROVIDED_BY") "SUBCO")
      )
      (libsource (lib "MCD_PARTS_database") (part "SB_OFF"))
    )
    (comp (ref "T1")
      (value "STL6N2VH5")
      (footprint "MOS_POWERFLAT_2X2_P065")
      (description "N-channel 20 V, 0.025 O typ., 6 A STripFET™ V Power MOSFET in a PowerFLAT™ 2x2 package")
      (fields
        (field (name "INTERNAL_PART_NUMBER") "MCD-01028")
        (field (name "MANUFACTURER") "STMICROELECTRONICS")
        (field (name "PROVIDED_BY") "SUBCO with ST control")
      )
      (libsource (lib "MCD_PARTS_database") (part "STL6N2VH5"))
    )
    (comp (ref "T2")
      (value "STL6N2VH5")
      (footprint "MOS_POWERFLAT_2X2_P065")
      (description "N-channel 20 V, 0.025 O typ., 6 A STripFET™ V Power MOSFET in a PowerFLAT™ 2x2 package")
      (fields
        (field (name "INTERNAL_PART_NUMBER") "MCD-01028")
        (field (name "MANUFACTURER") "STMICROELECTRONICS")
        (field (name "PROVIDED_BY") "SUBCO with ST control")
      )
      (libsource (lib "MCD_PARTS_database") (part "STL6N2VH5"))
    )
    (comp (ref "T3")
      (value "750317809")
      (footprint "TRS_WURTH_750317809")
      (description "Current Sense Transformer, 1:250 ratio, xx mohm / 20 ohms, 11mH, 10A")
      (fields
        (field (name "INTERNAL_PART_NUMBER") "MCD-01596")
        (field (name "MANUFACTURER") "WURTH ELEKTRONIK")
        (field (name "PROVIDED_BY") "SUBCO")
      )
      (libsource (lib "MCD_PARTS_database") (part "TRS_750317809"))
    )
    (comp (ref "T4")
      (value "749251125")
      (footprint "TRS_WURTH_749251125")
      (description "Current Sense Transformer, 1:125 ratio, 6 mohm / 6.5 ohms, 3mH, 10A")
      (fields
        (field (name "INTERNAL_PART_NUMBER") "MCD-01570")
        (field (name "MANUFACTURER") "WURTH ELEKTRONIK")
        (field (name "PROVIDED_BY") "SUBCO")
      )
      (libsource (lib "MCD_PARTS_database") (part "TRS_749251125"))
    )
    (comp (ref "T5")
      (value "STT4P3LLH6")
      (footprint "MOS_SOT23-6L")
      (description "Power MOSFET - P-Channel 30 V, 0.048 ? typ., 4 A STripFET H6 DeepGATE - SOT23-6L")
      (fields
        (field (name "INTERNAL_PART_NUMBER") "MCD-00574")
        (field (name "MANUFACTURER") "STMICROELECTRONICS")
        (field (name "PROVIDED_BY") "SUBCO with ST control")
      )
      (libsource (lib "MCD_PARTS_database") (part "STT4P3LLH6"))
    )
    (comp (ref "T6")
      (value "STT4P3LLH6")
      (footprint "MOS_SOT23-6L")
      (description "Power MOSFET - P-Channel 30 V, 0.048 ? typ., 4 A STripFET H6 DeepGATE - SOT23-6L")
      (fields
        (field (name "INTERNAL_PART_NUMBER") "MCD-00574")
        (field (name "MANUFACTURER") "STMICROELECTRONICS")
        (field (name "PROVIDED_BY") "SUBCO with ST control")
      )
      (libsource (lib "MCD_PARTS_database") (part "STT4P3LLH6"))
    )
    (comp (ref "T7")
      (value "STL6N2VH5")
      (footprint "MOS_POWERFLAT_2X2_P065")
      (description "N-channel 20 V, 0.025 O typ., 6 A STripFET™ V Power MOSFET in a PowerFLAT™ 2x2 package")
      (fields
        (field (name "INTERNAL_PART_NUMBER") "MCD-01028")
        (field (name "MANUFACTURER") "STMICROELECTRONICS")
        (field (name "PROVIDED_BY") "SUBCO with ST control")
      )
      (libsource (lib "MCD_PARTS_database") (part "STL6N2VH5"))
    )
    (comp (ref "T8")
      (value "STL6N2VH5")
      (footprint "MOS_POWERFLAT_2X2_P065")
      (description "N-channel 20 V, 0.025 O typ., 6 A STripFET™ V Power MOSFET in a PowerFLAT™ 2x2 package")
      (fields
        (field (name "INTERNAL_PART_NUMBER") "MCD-01028")
        (field (name "MANUFACTURER") "STMICROELECTRONICS")
        (field (name "PROVIDED_BY") "SUBCO with ST control")
      )
      (libsource (lib "MCD_PARTS_database") (part "STL6N2VH5"))
    )
    (comp (ref "TP1")
      (value "TP")
      (footprint "TP_PTH_1MM_2MM")
      (description "Test Point trought hole 1mm/2mm")
      (fields
        (field (name "INTERNAL_PART_NUMBER") "MCD-01506")
        (field (name "MANUFACTURER_PART_NUMBER") "n/a")
      )
      (libsource (lib "MCD_PARTS_database") (part "Test_Point_PTH_1mm_2mm"))
    )
    (comp (ref "TP2")
      (value "TP")
      (footprint "TP_PTH_1MM_2MM")
      (description "Test Point trought hole 1mm/2mm")
      (fields
        (field (name "INTERNAL_PART_NUMBER") "MCD-01506")
        (field (name "MANUFACTURER_PART_NUMBER") "n/a")
      )
      (libsource (lib "MCD_PARTS_database") (part "Test_Point_PTH_1mm_2mm"))
    )
  )
  (nets
    (net (code "15") (name "/1S") (class "Default")
      (node (ref "D1") (pin "2") (pinfunction "A_2") (pintype "passive"))
      (node (ref "R21") (pin "1") (pinfunction "1_1") (pintype "passive"))
      (node (ref "T3") (pin "1") (pinfunction "1_1") (pintype "passive"))
      (node (ref "T4") (pin "1") (pinfunction "1_1") (pintype "passive"))
    )
    (net (code "16") (name "/BUCKBOOST_I_IN_AVG") (class "Default")
      (node (ref "C1") (pin "2") (pinfunction "2_2") (pintype "passive"))
      (node (ref "R10") (pin "1") (pinfunction "1_1") (pintype "passive"))
    )
    (net (code "17") (name "/BUCKBOOST_LOAD_50%") (class "Default")
      (node (ref "R58") (pin "1") (pinfunction "1_1") (pintype "passive"))
    )
    (net (code "18") (name "/BUCKBOOST_LOAD_100%") (class "Default")
      (node (ref "R57") (pin "1") (pinfunction "1_1") (pintype "passive"))
    )
    (net (code "19") (name "/BUCKBOOST_N1_DRIVE") (class "Default")
      (node (ref "R19") (pin "1") (pinfunction "1_1") (pintype "passive"))
    )
    (net (code "20") (name "/BUCKBOOST_N2_DRIVE") (class "Default")
      (node (ref "R20") (pin "2") (pinfunction "2_2") (pintype "passive"))
    )
    (net (code "21") (name "/BUCKBOOST_P1_DRIVE") (class "Default")
      (node (ref "R3") (pin "1") (pinfunction "1_1") (pintype "passive"))
      (node (ref "R4") (pin "1") (pinfunction "1_1") (pintype "passive"))
    )
    (net (code "22") (name "/BUCKBOOST_P2_DRIVE") (class "Default")
      (node (ref "R5") (pin "2") (pinfunction "2_2") (pintype "passive"))
      (node (ref "R6") (pin "2") (pinfunction "2_2") (pintype "passive"))
    )
    (net (code "23") (name "/BUCKBOOST_USBPD_EN") (class "Default")
      (node (ref "Q14") (pin "1") (pinfunction "G_1") (pintype "passive"))
      (node (ref "R141") (pin "2") (pinfunction "2_2") (pintype "passive"))
    )
    (net (code "24") (name "/BUCKBOOST_VIN") (class "Default")
      (node (ref "C3") (pin "2") (pinfunction "2_2") (pintype "passive"))
      (node (ref "R11") (pin "2") (pinfunction "2_2") (pintype "passive"))
      (node (ref "R17") (pin "1") (pinfunction "1_1") (pintype "passive"))
    )
    (net (code "25") (name "/BUCKBOOST_VOUT") (class "Default")
      (node (ref "C2") (pin "2") (pinfunction "2_2") (pintype "passive"))
      (node (ref "R18") (pin "2") (pinfunction "2_2") (pintype "passive"))
      (node (ref "R22") (pin "1") (pinfunction "1_1") (pintype "passive"))
      (node (ref "R9") (pin "2") (pinfunction "2_2") (pintype "passive"))
    )
    (net (code "26") (name "/PC0") (class "Default")
      (node (ref "R2") (pin "1") (pinfunction "1_1") (pintype "passive"))
    )
    (net (code "27") (name "/PC1") (class "Default")
      (node (ref "R8") (pin "2") (pinfunction "2_2") (pintype "passive"))
    )
    (net (code "29") (name "AGND") (class "Default")
      (node (ref "C1") (pin "1") (pinfunction "1_1") (pintype "passive"))
      (node (ref "C2") (pin "1") (pinfunction "1_1") (pintype "passive"))
      (node (ref "C3") (pin "1") (pinfunction "1_1") (pintype "passive"))
      (node (ref "R11") (pin "1") (pinfunction "1_1") (pintype "passive"))
      (node (ref "R16") (pin "2") (pinfunction "2_2") (pintype "passive"))
      (node (ref "R18") (pin "1") (pinfunction "1_1") (pintype "passive"))
      (node (ref "R21") (pin "2") (pinfunction "2_2") (pintype "passive"))
      (node (ref "R9") (pin "1") (pinfunction "1_1") (pintype "passive"))
      (node (ref "SB1") (pin "1") (pinfunction "1_1") (pintype "passive"))
      (node (ref "T3") (pin "3") (pinfunction "3_3") (pintype "passive"))
      (node (ref "T4") (pin "3") (pinfunction "3_3") (pintype "passive"))
    )
    (net (code "30") (name "GND") (class "Default")
      (node (ref "C4") (pin "1") (pinfunction "1_1") (pintype "passive"))
      (node (ref "C5") (pin "1") (pinfunction "1_1") (pintype "passive"))
      (node (ref "C6") (pin "1") (pinfunction "1_1") (pintype "passive"))
      (node (ref "C7") (pin "2") (pinfunction "2_2") (pintype "passive"))
      (node (ref "C8") (pin "1") (pinfunction "1_1") (pintype "passive"))
      (node (ref "C9") (pin "1") (pinfunction "1_1") (pintype "passive"))
      (node (ref "CN7") (pin "2") (pinfunction "2_2") (pintype "passive"))
      (node (ref "JP1") (pin "3") (pinfunction "3_3") (pintype "passive"))
      (node (ref "Q1") (pin "2") (pinfunction "S_2") (pintype "passive"))
      (node (ref "Q14") (pin "2") (pinfunction "S_2") (pintype "passive"))
      (node (ref "Q2") (pin "2") (pinfunction "S_2") (pintype "passive"))
      (node (ref "Q3") (pin "2") (pinfunction "S_2") (pintype "passive"))
      (node (ref "Q4") (pin "2") (pinfunction "S_2") (pintype "passive"))
      (node (ref "Q5") (pin "3") (pinfunction "C_3") (pintype "passive"))
      (node (ref "Q6") (pin "3") (pinfunction "C_3") (pintype "passive"))
      (node (ref "R1") (pin "1") (pinfunction "1_1") (pintype "passive"))
      (node (ref "R12") (pin "1") (pinfunction "1_1") (pintype "passive"))
      (node (ref "R13") (pin "1") (pinfunction "1_1") (pintype "passive"))
      (node (ref "R141") (pin "1") (pinfunction "1_1") (pintype "passive"))
      (node (ref "R59") (pin "1") (pinfunction "1_1") (pintype "passive"))
      (node (ref "R60") (pin "1") (pinfunction "1_1") (pintype "passive"))
      (node (ref "R7") (pin "1") (pinfunction "1_1") (pintype "passive"))
      (node (ref "SB1") (pin "2") (pinfunction "2_2") (pintype "passive"))
      (node (ref "T1") (pin "4") (pinfunction "S_4") (pintype "passive"))
      (node (ref "T1") (pin "7") (pinfunction "S_7") (pintype "passive"))
      (node (ref "T2") (pin "4") (pinfunction "S_4") (pintype "passive"))
      (node (ref "T2") (pin "7") (pinfunction "S_7") (pintype "passive"))
      (node (ref "T7") (pin "4") (pinfunction "S_4") (pintype "passive"))
      (node (ref "T7") (pin "7") (pinfunction "S_7") (pintype "passive"))
      (node (ref "T8") (pin "4") (pinfunction "S_4") (pintype "passive"))
      (node (ref "T8") (pin "7") (pinfunction "S_7") (pintype "passive"))
    )
    (net (code "31") (name "Net-(C102-Pad2)") (class "Default")
      (node (ref "C102") (pin "2") (pinfunction "2_2") (pintype "passive"))
      (node (ref "Q12") (pin "1") (pinfunction "S_1") (pintype "passive"))
      (node (ref "Q12") (pin "2") (pinfunction "S_2") (pintype "passive"))
      (node (ref "Q12") (pin "3") (pinfunction "S_3") (pintype "passive"))
      (node (ref "Q13") (pin "1") (pinfunction "S_1") (pintype "passive"))
      (node (ref "Q13") (pin "2") (pinfunction "S_2") (pintype "passive"))
      (node (ref "Q13") (pin "3") (pinfunction "S_3") (pintype "passive"))
      (node (ref "R140") (pin "1") (pinfunction "1_1") (pintype "passive"))
    )
    (net (code "32") (name "Net-(D1-K)") (class "Default")
      (node (ref "D1") (pin "1") (pinfunction "K_1") (pintype "passive"))
      (node (ref "R10") (pin "2") (pinfunction "2_2") (pintype "passive"))
      (node (ref "R16") (pin "1") (pinfunction "1_1") (pintype "passive"))
    )
    (net (code "33") (name "Net-(D2-A)") (class "Default")
      (node (ref "D2") (pin "1") (pinfunction "A_1") (pintype "passive"))
      (node (ref "R15") (pin "1") (pinfunction "1_1") (pintype "passive"))
    )
    (net (code "34") (name "Net-(D2-K)") (class "Default")
      (node (ref "D2") (pin "3") (pinfunction "K_3") (pintype "passive"))
      (node (ref "D3") (pin "1") (pinfunction "A_1") (pintype "passive"))
      (node (ref "R14") (pin "1") (pinfunction "1_1") (pintype "passive"))
      (node (ref "T6") (pin "3") (pinfunction "G_3") (pintype "passive"))
    )
    (net (code "35") (name "Net-(D4-A)") (class "Default")
      (node (ref "D4") (pin "1") (pinfunction "A_1") (pintype "passive"))
      (node (ref "R28") (pin "2") (pinfunction "2_2") (pintype "passive"))
    )
    (net (code "36") (name "Net-(D4-K)") (class "Default")
      (node (ref "D4") (pin "3") (pinfunction "K_3") (pintype "passive"))
      (node (ref "D5") (pin "1") (pinfunction "A_1") (pintype "passive"))
      (node (ref "R27") (pin "2") (pinfunction "2_2") (pintype "passive"))
      (node (ref "T5") (pin "3") (pinfunction "G_3") (pintype "passive"))
    )
    (net (code "37") (name "Net-(F1-Pad1)") (class "Default")
      (node (ref "F1") (pin "1") (pinfunction "1_1") (pintype "passive"))
      (node (ref "R40") (pin "2") (pinfunction "2_2") (pintype "passive"))
      (node (ref "R48") (pin "2") (pinfunction "2_2") (pintype "passive"))
      (node (ref "R56") (pin "2") (pinfunction "2_2") (pintype "passive"))
      (node (ref "R64") (pin "2") (pinfunction "2_2") (pintype "passive"))
    )
    (net (code "38") (name "Net-(F2-Pad1)") (class "Default")
      (node (ref "F2") (pin "1") (pinfunction "1_1") (pintype "passive"))
      (node (ref "R32") (pin "2") (pinfunction "2_2") (pintype "passive"))
      (node (ref "R36") (pin "2") (pinfunction "2_2") (pintype "passive"))
      (node (ref "R44") (pin "2") (pinfunction "2_2") (pintype "passive"))
      (node (ref "R52") (pin "2") (pinfunction "2_2") (pintype "passive"))
    )
    (net (code "39") (name "Net-(JP2-COMMON)") (class "Default")
      (node (ref "JP2") (pin "1") (pinfunction "COMMON_1") (pintype "passive"))
      (node (ref "R24") (pin "1") (pinfunction "1_1") (pintype "passive"))
      (node (ref "T1") (pin "1") (pinfunction "D_1") (pintype "passive"))
      (node (ref "T1") (pin "2") (pinfunction "D_2") (pintype "passive"))
      (node (ref "T1") (pin "5") (pinfunction "D_5") (pintype "passive"))
      (node (ref "T1") (pin "6") (pinfunction "D_6") (pintype "passive"))
      (node (ref "T1") (pin "8") (pinfunction "D_8") (pintype "passive"))
      (node (ref "T5") (pin "1") (pinfunction "S_1") (pintype "passive"))
      (node (ref "T5") (pin "2") (pinfunction "S_2") (pintype "passive"))
      (node (ref "T5") (pin "5") (pinfunction "D_5") (pintype "passive"))
      (node (ref "T5") (pin "6") (pinfunction "D_6") (pintype "passive"))
    )
    (net (code "40") (name "Net-(JP2-NO)") (class "Default")
      (node (ref "JP2") (pin "2") (pinfunction "NO_2") (pintype "passive"))
      (node (ref "L1") (pin "2") (pinfunction "2_2") (pintype "passive"))
      (node (ref "R24") (pin "2") (pinfunction "2_2") (pintype "passive"))
    )
    (net (code "41") (name "Net-(JP3-COMMON)") (class "Default")
      (node (ref "JP3") (pin "1") (pinfunction "COMMON_1") (pintype "passive"))
      (node (ref "L1") (pin "1") (pinfunction "1_1") (pintype "passive"))
      (node (ref "R25") (pin "1") (pinfunction "1_1") (pintype "passive"))
    )
    (net (code "42") (name "Net-(JP3-NO)") (class "Default")
      (node (ref "JP3") (pin "2") (pinfunction "NO_2") (pintype "passive"))
      (node (ref "R25") (pin "2") (pinfunction "2_2") (pintype "passive"))
      (node (ref "T2") (pin "1") (pinfunction "D_1") (pintype "passive"))
      (node (ref "T2") (pin "2") (pinfunction "D_2") (pintype "passive"))
      (node (ref "T2") (pin "5") (pinfunction "D_5") (pintype "passive"))
      (node (ref "T2") (pin "6") (pinfunction "D_6") (pintype "passive"))
      (node (ref "T2") (pin "8") (pinfunction "D_8") (pintype "passive"))
      (node (ref "T6") (pin "1") (pinfunction "S_1") (pintype "passive"))
      (node (ref "T6") (pin "2") (pinfunction "S_2") (pintype "passive"))
      (node (ref "T6") (pin "5") (pinfunction "D_5") (pintype "passive"))
      (node (ref "T6") (pin "6") (pinfunction "D_6") (pintype "passive"))
    )
    (net (code "43") (name "Net-(Q1-D)") (class "Default")
      (node (ref "Q1") (pin "3") (pinfunction "D_3") (pintype "passive"))
      (node (ref "Q5") (pin "1") (pinfunction "B_1") (pintype "passive"))
      (node (ref "Q7") (pin "1") (pinfunction "B_1") (pintype "passive"))
      (node (ref "R23") (pin "1") (pinfunction "1_1") (pintype "passive"))
    )
    (net (code "44") (name "Net-(Q1-G)") (class "Default")
      (node (ref "Q1") (pin "1") (pinfunction "G_1") (pintype "passive"))
      (node (ref "R1") (pin "2") (pinfunction "2_2") (pintype "passive"))
      (node (ref "R2") (pin "2") (pinfunction "2_2") (pintype "passive"))
      (node (ref "R3") (pin "2") (pinfunction "2_2") (pintype "passive"))
    )
    (net (code "45") (name "Net-(Q2-D)") (class "Default")
      (node (ref "Q2") (pin "3") (pinfunction "D_3") (pintype "passive"))
      (node (ref "R12") (pin "2") (pinfunction "2_2") (pintype "passive"))
      (node (ref "R19") (pin "2") (pinfunction "2_2") (pintype "passive"))
      (node (ref "T1") (pin "3") (pinfunction "G_3") (pintype "passive"))
    )
    (net (code "46") (name "Net-(Q2-G)") (class "Default")
      (node (ref "Q2") (pin "1") (pinfunction "G_1") (pintype "passive"))
      (node (ref "R4") (pin "2") (pinfunction "2_2") (pintype "passive"))
    )
    (net (code "47") (name "Net-(Q3-D)") (class "Default")
      (node (ref "Q3") (pin "3") (pinfunction "D_3") (pintype "passive"))
      (node (ref "R13") (pin "2") (pinfunction "2_2") (pintype "passive"))
      (node (ref "R20") (pin "1") (pinfunction "1_1") (pintype "passive"))
      (node (ref "T2") (pin "3") (pinfunction "G_3") (pintype "passive"))
    )
    (net (code "48") (name "Net-(Q3-G)") (class "Default")
      (node (ref "Q3") (pin "1") (pinfunction "G_1") (pintype "passive"))
      (node (ref "R5") (pin "1") (pinfunction "1_1") (pintype "passive"))
    )
    (net (code "49") (name "Net-(Q4-D)") (class "Default")
      (node (ref "Q4") (pin "3") (pinfunction "D_3") (pintype "passive"))
      (node (ref "Q6") (pin "1") (pinfunction "B_1") (pintype "passive"))
      (node (ref "Q8") (pin "1") (pinfunction "B_1") (pintype "passive"))
      (node (ref "R26") (pin "1") (pinfunction "1_1") (pintype "passive"))
    )
    (net (code "50") (name "Net-(Q4-G)") (class "Default")
      (node (ref "Q4") (pin "1") (pinfunction "G_1") (pintype "passive"))
      (node (ref "R6") (pin "1") (pinfunction "1_1") (pintype "passive"))
      (node (ref "R7") (pin "2") (pinfunction "2_2") (pintype "passive"))
      (node (ref "R8") (pin "1") (pinfunction "1_1") (pintype "passive"))
    )
    (net (code "51") (name "Net-(Q5-E)") (class "Default")
      (node (ref "Q5") (pin "2") (pinfunction "E_2") (pintype "passive"))
      (node (ref "Q7") (pin "2") (pinfunction "E_2") (pintype "passive"))
      (node (ref "R27") (pin "1") (pinfunction "1_1") (pintype "passive"))
      (node (ref "R28") (pin "1") (pinfunction "1_1") (pintype "passive"))
    )
    (net (code "52") (name "Net-(Q6-E)") (class "Default")
      (node (ref "Q6") (pin "2") (pinfunction "E_2") (pintype "passive"))
      (node (ref "Q8") (pin "2") (pinfunction "E_2") (pintype "passive"))
      (node (ref "R14") (pin "2") (pinfunction "2_2") (pintype "passive"))
      (node (ref "R15") (pin "2") (pinfunction "2_2") (pintype "passive"))
    )
    (net (code "53") (name "Net-(Q12-G)") (class "Default")
      (node (ref "C102") (pin "1") (pinfunction "1_1") (pintype "passive"))
      (node (ref "Q12") (pin "4") (pinfunction "G_4") (pintype "passive"))
      (node (ref "Q13") (pin "4") (pinfunction "G_4") (pintype "passive"))
      (node (ref "R140") (pin "2") (pinfunction "2_2") (pintype "passive"))
      (node (ref "R142") (pin "2") (pinfunction "2_2") (pintype "passive"))
    )
    (net (code "54") (name "Net-(Q14-D)") (class "Default")
      (node (ref "Q14") (pin "3") (pinfunction "D_3") (pintype "passive"))
      (node (ref "R142") (pin "1") (pinfunction "1_1") (pintype "passive"))
    )
    (net (code "55") (name "Net-(R29-Pad1)") (class "Default")
      (node (ref "R29") (pin "1") (pinfunction "1_1") (pintype "passive"))
      (node (ref "R33") (pin "1") (pinfunction "1_1") (pintype "passive"))
      (node (ref "R41") (pin "1") (pinfunction "1_1") (pintype "passive"))
      (node (ref "R49") (pin "1") (pinfunction "1_1") (pintype "passive"))
      (node (ref "T7") (pin "1") (pinfunction "D_1") (pintype "passive"))
      (node (ref "T7") (pin "2") (pinfunction "D_2") (pintype "passive"))
      (node (ref "T7") (pin "5") (pinfunction "D_5") (pintype "passive"))
      (node (ref "T7") (pin "6") (pinfunction "D_6") (pintype "passive"))
      (node (ref "T7") (pin "8") (pinfunction "D_8") (pintype "passive"))
      (node (ref "TP1") (pin "1") (pinfunction "1_1") (pintype "passive"))
    )
    (net (code "56") (name "Net-(R29-Pad2)") (class "Default")
      (node (ref "R29") (pin "2") (pinfunction "2_2") (pintype "passive"))
      (node (ref "R30") (pin "1") (pinfunction "1_1") (pintype "passive"))
      (node (ref "R33") (pin "2") (pinfunction "2_2") (pintype "passive"))
      (node (ref "R34") (pin "1") (pinfunction "1_1") (pintype "passive"))
      (node (ref "R41") (pin "2") (pinfunction "2_2") (pintype "passive"))
      (node (ref "R42") (pin "1") (pinfunction "1_1") (pintype "passive"))
      (node (ref "R49") (pin "2") (pinfunction "2_2") (pintype "passive"))
      (node (ref "R50") (pin "1") (pinfunction "1_1") (pintype "passive"))
    )
    (net (code "57") (name "Net-(R30-Pad2)") (class "Default")
      (node (ref "R30") (pin "2") (pinfunction "2_2") (pintype "passive"))
      (node (ref "R31") (pin "1") (pinfunction "1_1") (pintype "passive"))
      (node (ref "R34") (pin "2") (pinfunction "2_2") (pintype "passive"))
      (node (ref "R35") (pin "1") (pinfunction "1_1") (pintype "passive"))
      (node (ref "R42") (pin "2") (pinfunction "2_2") (pintype "passive"))
      (node (ref "R43") (pin "1") (pinfunction "1_1") (pintype "passive"))
      (node (ref "R50") (pin "2") (pinfunction "2_2") (pintype "passive"))
      (node (ref "R51") (pin "1") (pinfunction "1_1") (pintype "passive"))
    )
    (net (code "58") (name "Net-(R31-Pad2)") (class "Default")
      (node (ref "R31") (pin "2") (pinfunction "2_2") (pintype "passive"))
      (node (ref "R32") (pin "1") (pinfunction "1_1") (pintype "passive"))
      (node (ref "R35") (pin "2") (pinfunction "2_2") (pintype "passive"))
      (node (ref "R36") (pin "1") (pinfunction "1_1") (pintype "passive"))
      (node (ref "R43") (pin "2") (pinfunction "2_2") (pintype "passive"))
      (node (ref "R44") (pin "1") (pinfunction "1_1") (pintype "passive"))
      (node (ref "R51") (pin "2") (pinfunction "2_2") (pintype "passive"))
      (node (ref "R52") (pin "1") (pinfunction "1_1") (pintype "passive"))
    )
    (net (code "59") (name "Net-(R37-Pad1)") (class "Default")
      (node (ref "R37") (pin "1") (pinfunction "1_1") (pintype "passive"))
      (node (ref "R45") (pin "1") (pinfunction "1_1") (pintype "passive"))
      (node (ref "R53") (pin "1") (pinfunction "1_1") (pintype "passive"))
      (node (ref "R61") (pin "1") (pinfunction "1_1") (pintype "passive"))
      (node (ref "T8") (pin "1") (pinfunction "D_1") (pintype "passive"))
      (node (ref "T8") (pin "2") (pinfunction "D_2") (pintype "passive"))
      (node (ref "T8") (pin "5") (pinfunction "D_5") (pintype "passive"))
      (node (ref "T8") (pin "6") (pinfunction "D_6") (pintype "passive"))
      (node (ref "T8") (pin "8") (pinfunction "D_8") (pintype "passive"))
      (node (ref "TP2") (pin "1") (pinfunction "1_1") (pintype "passive"))
    )
    (net (code "60") (name "Net-(R37-Pad2)") (class "Default")
      (node (ref "R37") (pin "2") (pinfunction "2_2") (pintype "passive"))
      (node (ref "R38") (pin "1") (pinfunction "1_1") (pintype "passive"))
      (node (ref "R45") (pin "2") (pinfunction "2_2") (pintype "passive"))
      (node (ref "R46") (pin "1") (pinfunction "1_1") (pintype "passive"))
      (node (ref "R53") (pin "2") (pinfunction "2_2") (pintype "passive"))
      (node (ref "R54") (pin "1") (pinfunction "1_1") (pintype "passive"))
      (node (ref "R61") (pin "2") (pinfunction "2_2") (pintype "passive"))
      (node (ref "R62") (pin "1") (pinfunction "1_1") (pintype "passive"))
    )
    (net (code "61") (name "Net-(R38-Pad2)") (class "Default")
      (node (ref "R38") (pin "2") (pinfunction "2_2") (pintype "passive"))
      (node (ref "R39") (pin "1") (pinfunction "1_1") (pintype "passive"))
      (node (ref "R46") (pin "2") (pinfunction "2_2") (pintype "passive"))
      (node (ref "R47") (pin "1") (pinfunction "1_1") (pintype "passive"))
      (node (ref "R54") (pin "2") (pinfunction "2_2") (pintype "passive"))
      (node (ref "R55") (pin "1") (pinfunction "1_1") (pintype "passive"))
      (node (ref "R62") (pin "2") (pinfunction "2_2") (pintype "passive"))
      (node (ref "R63") (pin "1") (pinfunction "1_1") (pintype "passive"))
    )
    (net (code "62") (name "Net-(R39-Pad2)") (class "Default")
      (node (ref "R39") (pin "2") (pinfunction "2_2") (pintype "passive"))
      (node (ref "R40") (pin "1") (pinfunction "1_1") (pintype "passive"))
      (node (ref "R47") (pin "2") (pinfunction "2_2") (pintype "passive"))
      (node (ref "R48") (pin "1") (pinfunction "1_1") (pintype "passive"))
      (node (ref "R55") (pin "2") (pinfunction "2_2") (pintype "passive"))
      (node (ref "R56") (pin "1") (pinfunction "1_1") (pintype "passive"))
      (node (ref "R63") (pin "2") (pinfunction "2_2") (pintype "passive"))
      (node (ref "R64") (pin "1") (pinfunction "1_1") (pintype "passive"))
    )
    (net (code "63") (name "Net-(T7-G)") (class "Default")
      (node (ref "R57") (pin "2") (pinfunction "2_2") (pintype "passive"))
      (node (ref "R59") (pin "2") (pinfunction "2_2") (pintype "passive"))
      (node (ref "T7") (pin "3") (pinfunction "G_3") (pintype "passive"))
    )
    (net (code "64") (name "Net-(T8-G)") (class "Default")
      (node (ref "R58") (pin "2") (pinfunction "2_2") (pintype "passive"))
      (node (ref "R60") (pin "2") (pinfunction "2_2") (pintype "passive"))
      (node (ref "T8") (pin "3") (pinfunction "G_3") (pintype "passive"))
    )
    (net (code "65") (name "USBPD_VBUS") (class "Default")
      (node (ref "Q12") (pin "5") (pinfunction "D_5") (pintype "passive"))
      (node (ref "Q12") (pin "6") (pinfunction "D_6") (pintype "passive"))
      (node (ref "Q12") (pin "7") (pinfunction "D_7") (pintype "passive"))
      (node (ref "Q12") (pin "8") (pinfunction "D_8") (pintype "passive"))
    )
    (net (code "66") (name "USB_PD_VBUS") (class "Default")
      (node (ref "JP1") (pin "1") (pinfunction "1_1") (pintype "passive"))
      (node (ref "Q13") (pin "5") (pinfunction "D_5") (pintype "passive"))
      (node (ref "Q13") (pin "6") (pinfunction "D_6") (pintype "passive"))
      (node (ref "Q13") (pin "7") (pinfunction "D_7") (pintype "passive"))
      (node (ref "Q13") (pin "8") (pinfunction "D_8") (pintype "passive"))
    )
    (net (code "67") (name "VIN") (class "Default")
      (node (ref "C4") (pin "2") (pinfunction "2_2") (pintype "passive"))
      (node (ref "C8") (pin "2") (pinfunction "2_2") (pintype "passive"))
      (node (ref "JP1") (pin "2") (pinfunction "2_2") (pintype "passive"))
      (node (ref "T3") (pin "8") (pinfunction "8_8") (pintype "passive"))
      (node (ref "T4") (pin "8") (pinfunction "8_8") (pintype "passive"))
    )
    (net (code "68") (name "VOUT") (class "Default")
      (node (ref "C5") (pin "2") (pinfunction "2_2") (pintype "passive"))
      (node (ref "C7") (pin "1") (pinfunction "1_1") (pintype "passive"))
      (node (ref "C9") (pin "2") (pinfunction "2_2") (pintype "passive"))
      (node (ref "CN7") (pin "1") (pinfunction "1_1") (pintype "passive"))
      (node (ref "D3") (pin "2") (pinfunction "K_2") (pintype "passive"))
      (node (ref "F1") (pin "2") (pinfunction "2_2") (pintype "passive"))
      (node (ref "F2") (pin "2") (pinfunction "2_2") (pintype "passive"))
      (node (ref "Q8") (pin "3") (pinfunction "C_3") (pintype "passive"))
      (node (ref "R132") (pin "2") (pinfunction "2_2") (pintype "passive"))
      (node (ref "R22") (pin "2") (pinfunction "2_2") (pintype "passive"))
      (node (ref "R26") (pin "2") (pinfunction "2_2") (pintype "passive"))
      (node (ref "T6") (pin "4") (pinfunction "S_4") (pintype "passive"))
    )
    (net (code "69") (name "V_IN") (class "Default")
      (node (ref "C6") (pin "2") (pinfunction "2_2") (pintype "passive"))
      (node (ref "D5") (pin "2") (pinfunction "K_2") (pintype "passive"))
      (node (ref "Q7") (pin "3") (pinfunction "C_3") (pintype "passive"))
      (node (ref "R132") (pin "1") (pinfunction "1_1") (pintype "passive"))
      (node (ref "R17") (pin "2") (pinfunction "2_2") (pintype "passive"))
      (node (ref "R23") (pin "2") (pinfunction "2_2") (pintype "passive"))
      (node (ref "T3") (pin "7") (pinfunction "7_7") (pintype "passive"))
      (node (ref "T4") (pin "7") (pinfunction "7_7") (pintype "passive"))
      (node (ref "T5") (pin "4") (pinfunction "S_4") (pintype "passive"))
    )
    (net (code "70") (name "unconnected-(T3-Pad2)") (class "Default")
      (node (ref "T3") (pin "2") (pinfunction "2_2") (pintype "passive+no_connect"))
    )
    (net (code "71") (name "unconnected-(T3-Pad4)") (class "Default")
      (node (ref "T3") (pin "4") (pinfunction "4_4") (pintype "passive+no_connect"))
    )
    (net (code "72") (name "unconnected-(T3-Pad5)") (class "Default")
      (node (ref "T3") (pin "5") (pinfunction "5_5") (pintype "passive+no_connect"))
    )
    (net (code "73") (name "unconnected-(T3-Pad6)") (class "Default")
      (node (ref "T3") (pin "6") (pinfunction "6_6") (pintype "passive+no_connect"))
    )
    (net (code "74") (name "unconnected-(T4-Pad2)") (class "Default")
      (node (ref "T4") (pin "2") (pinfunction "2_2") (pintype "passive+no_connect"))
    )
    (net (code "75") (name "unconnected-(T4-Pad4)") (class "Default")
      (node (ref "T4") (pin "4") (pinfunction "4_4") (pintype "passive+no_connect"))
    )
    (net (code "76") (name "unconnected-(T4-Pad5)") (class "Default")
      (node (ref "T4") (pin "5") (pinfunction "5_5") (pintype "passive+no_connect"))
    )
    (net (code "77") (name "unconnected-(T4-Pad6)") (class "Default")
      (node (ref "T4") (pin "6") (pinfunction "6_6") (pintype "passive+no_connect"))
    )
  )
)
